# DSP_2.net
KiCad netlist of a schematic drawn in Altium Designer
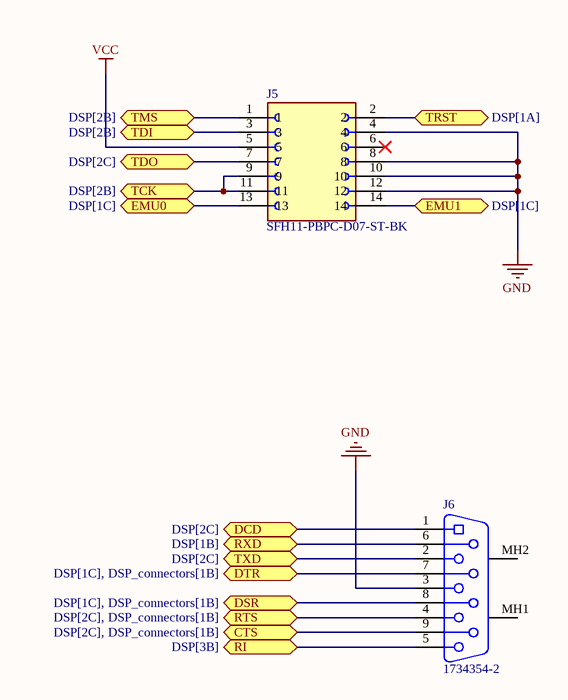
[diagram p0: DSP_2.SchDoc]

(export (version "E")
  (design (tool "Eeschema 10.0.6"))
  (components
    (comp (ref "J5")
      (value "SFH11-PBPC-D07-ST-BK")
      (footprint "SULLINS_SFH11-PBPC-D07-ST-BK")
      (description "14 Position Header Connector Through Hole")
      (fields (field (name "MF") "Sullins Connector"))
      (libsource (lib "SFH11-PBPC-D07-ST-BK") (part "SFH11-PBPC-D07-ST-BK"))
    )
    (comp (ref "J6")
      (value "1734354-2")
      (footprint "TECO-1734354-2_V")
      (fields (field (name "MANUFACTURER") "TE Connectivity"))
      (libsource (lib "Altium Content Vault") (part "CN-2S-2F-D9"))
    )
  )
  (nets
    (net (code "1") (name "/CTS") (class "Default")
      (node (ref "J6") (pin "9") (pinfunction "9_9") (pintype "passive"))
    )
    (net (code "2") (name "/DCD") (class "Default")
      (node (ref "J6") (pin "1") (pinfunction "1_1") (pintype "passive"))
    )
    (net (code "3") (name "/DSR") (class "Default")
      (node (ref "J6") (pin "8") (pinfunction "8_8") (pintype "passive"))
    )
    (net (code "4") (name "/DTR") (class "Default")
      (node (ref "J6") (pin "7") (pinfunction "7_7") (pintype "passive"))
    )
    (net (code "5") (name "/EMU0") (class "Default")
      (node (ref "J5") (pin "13") (pinfunction "13_13") (pintype "passive"))
    )
    (net (code "6") (name "/EMU1") (class "Default")
      (node (ref "J5") (pin "14") (pinfunction "14_14") (pintype "passive"))
    )
    (net (code "7") (name "/RI") (class "Default")
      (node (ref "J6") (pin "5") (pinfunction "5_5") (pintype "passive"))
    )
    (net (code "8") (name "/RTS") (class "Default")
      (node (ref "J6") (pin "4") (pinfunction "4_4") (pintype "passive"))
    )
    (net (code "9") (name "/RXD") (class "Default")
      (node (ref "J6") (pin "6") (pinfunction "6_6") (pintype "passive"))
    )
    (net (code "10") (name "/TCK") (class "Default")
      (node (ref "J5") (pin "11") (pinfunction "11_11") (pintype "passive"))
      (node (ref "J5") (pin "9") (pinfunction "9_9") (pintype "passive"))
    )
    (net (code "11") (name "/TDI") (class "Default")
      (node (ref "J5") (pin "3") (pinfunction "3_3") (pintype "passive"))
    )
    (net (code "12") (name "/TDO") (class "Default")
      (node (ref "J5") (pin "7") (pinfunction "7_7") (pintype "passive"))
    )
    (net (code "13") (name "/TMS") (class "Default")
      (node (ref "J5") (pin "1") (pinfunction "1_1") (pintype "passive"))
    )
    (net (code "14") (name "/TRST") (class "Default")
      (node (ref "J5") (pin "2") (pinfunction "2_2") (pintype "passive"))
    )
    (net (code "15") (name "/TXD") (class "Default")
      (node (ref "J6") (pin "2") (pinfunction "2_2") (pintype "passive"))
    )
    (net (code "16") (name "GND") (class "Default")
      (node (ref "J5") (pin "10") (pinfunction "10_10") (pintype "passive"))
      (node (ref "J5") (pin "12") (pinfunction "12_12") (pintype "passive"))
      (node (ref "J5") (pin "4") (pinfunction "4_4") (pintype "passive"))
      (node (ref "J5") (pin "8") (pinfunction "8_8") (pintype "passive"))
      (node (ref "J6") (pin "3") (pinfunction "3_3") (pintype "passive"))
    )
    (net (code "17") (name "VCC") (class "Default")
      (node (ref "J5") (pin "5") (pinfunction "5_5") (pintype "passive"))
    )
    (net (code "18") (name "unconnected-(J5-Pad6)") (class "Default")
      (node (ref "J5") (pin "6") (pinfunction "6_6") (pintype "passive+no_connect"))
    )
    (net (code "19") (name "unconnected-(J6-PadMH1)") (class "Default")
      (node (ref "J6") (pin "MH1") (pinfunction "MH1_MH1") (pintype "passive"))
    )
    (net (code "20") (name "unconnected-(J6-PadMH2)") (class "Default")
      (node (ref "J6") (pin "MH2") (pinfunction "MH2_MH2") (pintype "passive"))
    )
  )
)
